# Peak_Detector_-_channel.net
KiCad netlist of a schematic drawn in Altium Designer
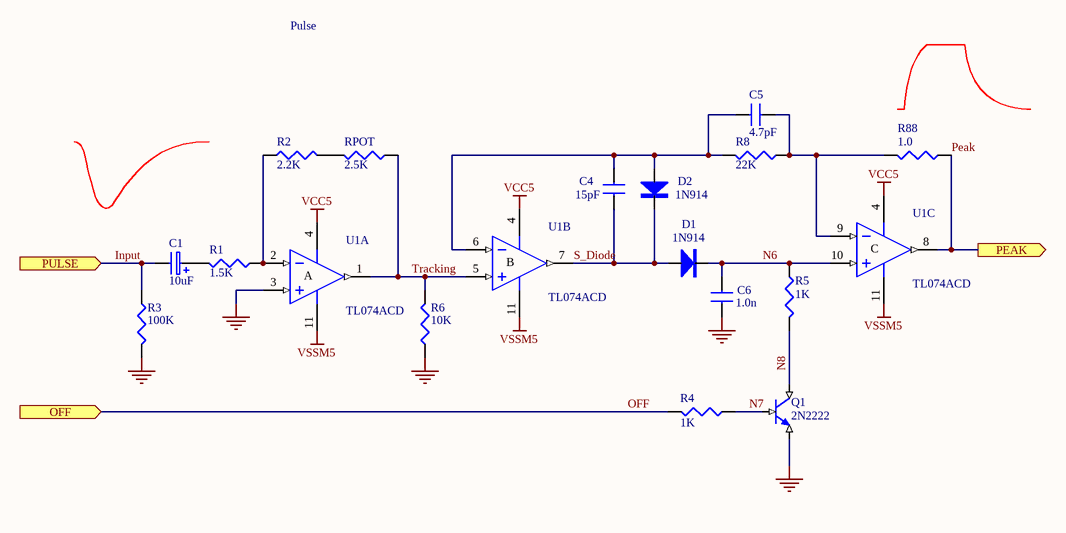
[diagram p0: Peak Detector - channel.SchDoc]

(export (version "E")
  (design (tool "Eeschema 10.0.6"))
  (components
    (comp (ref "C1")
      (value "10uF")
      (footprint "1206")
      (description "Capacitor")
      (libsource (lib "*") (part "CAP3"))
    )
    (comp (ref "C4")
      (value "15pF")
      (footprint "0805")
      (description "Capacitor")
      (libsource (lib "*") (part "CAP"))
    )
    (comp (ref "C5")
      (value "4.7pF")
      (footprint "0805")
      (description "Capacitor")
      (libsource (lib "*") (part "CAP"))
    )
    (comp (ref "C6")
      (value "1.0n")
      (footprint "0805")
      (description "Capacitor")
      (libsource (lib "*") (part "CAP"))
    )
    (comp (ref "D1")
      (value "1N914")
      (footprint "3216")
      (description "Diode")
      (libsource (lib "") (part "1N914_1"))
    )
    (comp (ref "D2")
      (value "1N914")
      (footprint "3216")
      (description "Diode")
      (libsource (lib "*") (part "1N914"))
    )
    (comp (ref "Q1")
      (value "2N2222")
      (footprint "SO-G3/D4.1")
      (description "NPN BJT")
      (libsource (lib "*") (part "2N2222"))
    )
    (comp (ref "R1")
      (value "1.5K")
      (footprint "0603")
      (description "Resistor")
      (libsource (lib "*") (part "RES"))
    )
    (comp (ref "R2")
      (value "2.2K")
      (footprint "0603")
      (description "Resistor")
      (libsource (lib "") (part "RES_1"))
    )
    (comp (ref "R3")
      (value "100K")
      (footprint "0603")
      (description "Resistor")
      (libsource (lib "") (part "RES_3"))
    )
    (comp (ref "R4")
      (value "1K")
      (footprint "0603")
      (description "Resistor")
      (fields (field (name "Comment") "10K"))
      (libsource (lib "*") (part "RES"))
    )
    (comp (ref "R5")
      (value "1K")
      (footprint "0603")
      (description "Resistor")
      (libsource (lib "") (part "RES_1"))
    )
    (comp (ref "R6")
      (value "10K")
      (footprint "0603")
      (description "Resistor")
      (libsource (lib "") (part "RES_2"))
    )
    (comp (ref "R8")
      (value "22K")
      (footprint "0603")
      (description "Resistor")
      (libsource (lib "*") (part "RES"))
    )
    (comp (ref "R88")
      (value "1.0")
      (footprint "0603")
      (description "Resistor")
      (libsource (lib "*") (part "RES"))
    )
    (comp (ref "RPOT")
      (value "2.5K")
      (footprint "0603")
      (description "Resistor")
      (libsource (lib "*") (part "RES"))
    )
    (comp (ref "U1")
      (value "TL074ACD")
      (footprint "SO-G14/G3")
      (description "Low-Noise J-FET Quad Operational Amplifier")
      (libsource (lib "ST-Microelectronics Sch") (part "TL074ACD"))
    )
  )
  (nets
    (net (code "1") (name "/Input") (class "Default")
      (node (ref "C1") (pin "2") (pinfunction "2_2") (pintype "passive"))
      (node (ref "R3") (pin "2") (pinfunction "BOT_2") (pintype "passive"))
    )
    (net (code "2") (name "/N6") (class "Default")
      (node (ref "C6") (pin "2") (pinfunction "2_2") (pintype "passive"))
      (node (ref "D1") (pin "2") (pinfunction "K_2") (pintype "passive"))
      (node (ref "R5") (pin "1") (pinfunction "TOP_1") (pintype "passive"))
      (node (ref "U1") (pin "10") (pinfunction "IN+_10") (pintype "input"))
    )
    (net (code "3") (name "/N7") (class "Default")
      (node (ref "Q1") (pin "2") (pinfunction "B_2") (pintype "input"))
      (node (ref "R4") (pin "2") (pinfunction "BOT_2") (pintype "passive"))
    )
    (net (code "4") (name "/N8") (class "Default")
      (node (ref "Q1") (pin "1") (pinfunction "C_1") (pintype "input"))
      (node (ref "R5") (pin "2") (pinfunction "BOT_2") (pintype "passive"))
    )
    (net (code "5") (name "/OFF") (class "Default")
      (node (ref "R4") (pin "1") (pinfunction "TOP_1") (pintype "passive"))
    )
    (net (code "6") (name "/Peak") (class "Default")
      (node (ref "R88") (pin "2") (pinfunction "BOT_2") (pintype "passive"))
      (node (ref "U1") (pin "8") (pinfunction "OUT_8") (pintype "output"))
    )
    (net (code "7") (name "/S_Diode") (class "Default")
      (node (ref "C4") (pin "2") (pinfunction "2_2") (pintype "passive"))
      (node (ref "D1") (pin "1") (pinfunction "A_1") (pintype "passive"))
      (node (ref "D2") (pin "2") (pinfunction "K_2") (pintype "passive"))
      (node (ref "U1") (pin "7") (pinfunction "OUT_7") (pintype "output"))
    )
    (net (code "8") (name "/Tracking") (class "Default")
      (node (ref "R6") (pin "1") (pinfunction "TOP_1") (pintype "passive"))
      (node (ref "RPOT") (pin "2") (pinfunction "BOT_2") (pintype "passive"))
      (node (ref "U1") (pin "1") (pinfunction "OUT_1") (pintype "output"))
      (node (ref "U1") (pin "5") (pinfunction "IN+_5") (pintype "input"))
    )
    (net (code "9") (name "GND") (class "Default")
      (node (ref "C6") (pin "1") (pinfunction "1_1") (pintype "passive"))
      (node (ref "Q1") (pin "3") (pinfunction "E_3") (pintype "input"))
      (node (ref "R3") (pin "1") (pinfunction "TOP_1") (pintype "passive"))
      (node (ref "R6") (pin "2") (pinfunction "BOT_2") (pintype "passive"))
      (node (ref "U1") (pin "3") (pinfunction "IN+_3") (pintype "input"))
    )
    (net (code "10") (name "Net-(D2-A)") (class "Default")
      (node (ref "C4") (pin "1") (pinfunction "1_1") (pintype "passive"))
      (node (ref "C5") (pin "1") (pinfunction "1_1") (pintype "passive"))
      (node (ref "D2") (pin "1") (pinfunction "A_1") (pintype "passive"))
      (node (ref "R8") (pin "1") (pinfunction "TOP_1") (pintype "passive"))
      (node (ref "U1") (pin "6") (pinfunction "IN-_6") (pintype "input"))
    )
    (net (code "11") (name "Net-(R1-BOT)") (class "Default")
      (node (ref "R1") (pin "2") (pinfunction "BOT_2") (pintype "passive"))
      (node (ref "R2") (pin "2") (pinfunction "BOT_2") (pintype "passive"))
      (node (ref "U1") (pin "2") (pinfunction "IN-_2") (pintype "input"))
    )
    (net (code "12") (name "Net-(R1-TOP)") (class "Default")
      (node (ref "C1") (pin "1") (pinfunction "1_1") (pintype "passive"))
      (node (ref "R1") (pin "1") (pinfunction "TOP_1") (pintype "passive"))
    )
    (net (code "13") (name "Net-(R2-TOP)") (class "Default")
      (node (ref "R2") (pin "1") (pinfunction "TOP_1") (pintype "passive"))
      (node (ref "RPOT") (pin "1") (pinfunction "TOP_1") (pintype "passive"))
    )
    (net (code "14") (name "Net-(R8-BOT)") (class "Default")
      (node (ref "C5") (pin "2") (pinfunction "2_2") (pintype "passive"))
      (node (ref "R8") (pin "2") (pinfunction "BOT_2") (pintype "passive"))
      (node (ref "R88") (pin "1") (pinfunction "TOP_1") (pintype "passive"))
      (node (ref "U1") (pin "9") (pinfunction "IN-_9") (pintype "input"))
    )
    (net (code "15") (name "VCC5") (class "Default")
      (node (ref "U1") (pin "4") (pinfunction "V+_4") (pintype "power_in"))
    )
    (net (code "16") (name "VSSM5") (class "Default")
      (node (ref "U1") (pin "11") (pinfunction "V-_11") (pintype "power_in"))
    )
  )
)
